# Audio.net
KiCad netlist of a schematic drawn in Altium Designer
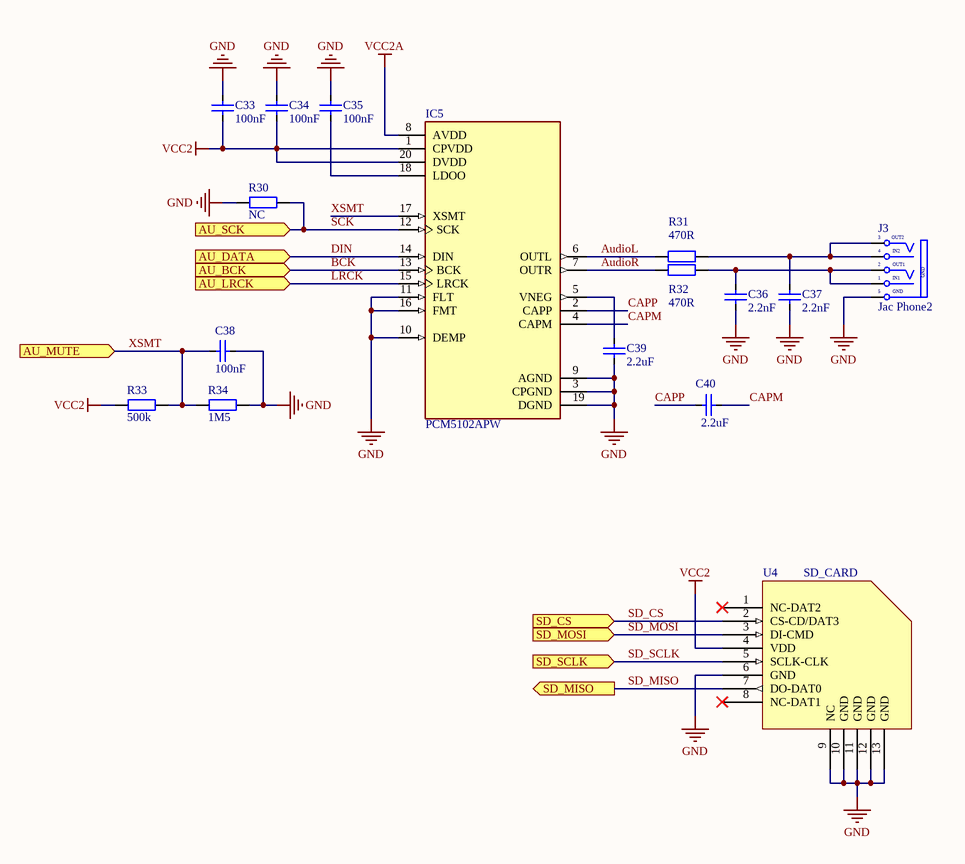
[diagram p0: Audio.SchDoc]

(export (version "E")
  (design (tool "Eeschema 10.0.6"))
  (components
    (comp (ref "C33")
      (value "100nF")
      (footprint "CAP_0603")
      (description "Capacitor")
      (fields (field (name "PUBLISHER") "Altium Limited"))
      (libsource (lib "My Library") (part "CapSMD"))
    )
    (comp (ref "C34")
      (value "100nF")
      (footprint "CAP_0603")
      (description "Capacitor")
      (fields (field (name "PUBLISHER") "Altium Limited"))
      (libsource (lib "My Library") (part "CapSMD"))
    )
    (comp (ref "C35")
      (value "100nF")
      (footprint "CAP_0603")
      (description "Capacitor")
      (fields (field (name "PUBLISHER") "Altium Limited"))
      (libsource (lib "My Library") (part "CapSMD"))
    )
    (comp (ref "C36")
      (value "2.2nF")
      (footprint "CAP_0603")
      (description "Capacitor")
      (fields (field (name "PUBLISHER") "Altium Limited"))
      (libsource (lib "My Library") (part "CapSMD"))
    )
    (comp (ref "C37")
      (value "2.2nF")
      (footprint "CAP_0603")
      (description "Capacitor")
      (fields (field (name "PUBLISHER") "Altium Limited"))
      (libsource (lib "My Library") (part "CapSMD"))
    )
    (comp (ref "C38")
      (value "100nF")
      (footprint "CAP_0603")
      (description "Capacitor")
      (fields (field (name "PUBLISHER") "Altium Limited"))
      (libsource (lib "My Library") (part "CapSMD"))
    )
    (comp (ref "C39")
      (value "2.2uF")
      (footprint "CAP_0603")
      (description "Capacitor")
      (fields (field (name "PUBLISHER") "Altium Limited"))
      (libsource (lib "My Library") (part "CapSMD"))
    )
    (comp (ref "C40")
      (value "2.2uF")
      (footprint "CAP_0603")
      (description "Capacitor")
      (fields (field (name "PUBLISHER") "Altium Limited"))
      (libsource (lib "My Library") (part "CapSMD"))
    )
    (comp (ref "IC5")
      (value "PCM5102APW")
      (footprint "TSSOP-20")
      (description "Audio decode")
      (libsource (lib "My Library") (part "PCM5102APW"))
    )
    (comp (ref "J3")
      (value "Jac Phone2")
      (footprint "JacPhone2")
      (description "Jac Phone Stereo")
      (fields (field (name "CREAT BY") "VanDungEvn@Gmail.com"))
      (libsource (lib "My Library") (part "Jac Phone2"))
    )
    (comp (ref "R30")
      (value "NC")
      (footprint "RES-SMD-0603")
      (description "Resistor SMD")
      (fields
        (field (name "MANUFACTURER") "Generic Components")
        (field (name "PUBLISHER") "Altium Hobart Technology Centre")
      )
      (libsource (lib "My Library") (part "Resistor - SMD"))
    )
    (comp (ref "R31")
      (value "470R")
      (footprint "RES-SMD-0603")
      (description "Resistor SMD")
      (fields
        (field (name "MANUFACTURER") "Generic Components")
        (field (name "PUBLISHER") "Altium Hobart Technology Centre")
      )
      (libsource (lib "My Library") (part "Resistor - SMD"))
    )
    (comp (ref "R32")
      (value "470R")
      (footprint "RES-SMD-0603")
      (description "Resistor SMD")
      (fields
        (field (name "MANUFACTURER") "Generic Components")
        (field (name "PUBLISHER") "Altium Hobart Technology Centre")
      )
      (libsource (lib "My Library") (part "Resistor - SMD"))
    )
    (comp (ref "R33")
      (value "500k")
      (footprint "RES-SMD-0603")
      (description "Resistor SMD")
      (fields
        (field (name "MANUFACTURER") "Generic Components")
        (field (name "PUBLISHER") "Altium Hobart Technology Centre")
      )
      (libsource (lib "My Library") (part "Resistor - SMD"))
    )
    (comp (ref "R34")
      (value "1M5")
      (footprint "RES-SMD-0603")
      (description "Resistor SMD")
      (fields
        (field (name "MANUFACTURER") "Generic Components")
        (field (name "PUBLISHER") "Altium Hobart Technology Centre")
      )
      (libsource (lib "My Library") (part "Resistor - SMD"))
    )
    (comp (ref "U4")
      (value "SD_CARD")
      (footprint "MICROSD2")
      (description "SD/MMC holder")
      (libsource (lib "My Library") (part "MicroSD"))
    )
  )
  (nets
    (net (code "1") (name "/AudioL") (class "Default")
      (node (ref "IC5") (pin "6") (pinfunction "OUTL_6") (pintype "output"))
      (node (ref "R31") (pin "2") (pinfunction "2_2") (pintype "passive"))
    )
    (net (code "2") (name "/AudioR") (class "Default")
      (node (ref "IC5") (pin "7") (pinfunction "OUTR_7") (pintype "output"))
      (node (ref "R32") (pin "2") (pinfunction "2_2") (pintype "passive"))
    )
    (net (code "3") (name "/BCK") (class "Default")
      (node (ref "IC5") (pin "13") (pinfunction "BCK_13") (pintype "input"))
    )
    (net (code "4") (name "/CAPM") (class "Default")
      (node (ref "C40") (pin "2") (pinfunction "2_2") (pintype "passive"))
      (node (ref "IC5") (pin "4") (pinfunction "CAPM_4") (pintype "passive"))
    )
    (net (code "5") (name "/CAPP") (class "Default")
      (node (ref "C40") (pin "1") (pinfunction "1_1") (pintype "passive"))
      (node (ref "IC5") (pin "2") (pinfunction "CAPP_2") (pintype "passive"))
    )
    (net (code "6") (name "/DIN") (class "Default")
      (node (ref "IC5") (pin "14") (pinfunction "DIN_14") (pintype "input"))
    )
    (net (code "7") (name "/LRCK") (class "Default")
      (node (ref "IC5") (pin "15") (pinfunction "LRCK_15") (pintype "input"))
    )
    (net (code "8") (name "/SCK") (class "Default")
      (node (ref "IC5") (pin "12") (pinfunction "SCK_12") (pintype "input"))
      (node (ref "R30") (pin "2") (pinfunction "2_2") (pintype "passive"))
    )
    (net (code "9") (name "/SD_CS") (class "Default")
      (node (ref "U4") (pin "2") (pinfunction "CS-CD/DAT3_2") (pintype "input"))
    )
    (net (code "10") (name "/SD_MISO") (class "Default")
      (node (ref "U4") (pin "7") (pinfunction "DO-DAT0_7") (pintype "output"))
    )
    (net (code "11") (name "/SD_MOSI") (class "Default")
      (node (ref "U4") (pin "3") (pinfunction "DI-CMD_3") (pintype "input"))
    )
    (net (code "12") (name "/SD_SCLK") (class "Default")
      (node (ref "U4") (pin "5") (pinfunction "SCLK-CLK_5") (pintype "input"))
    )
    (net (code "13") (name "/XSMT") (class "Default")
      (node (ref "C38") (pin "1") (pinfunction "1_1") (pintype "passive"))
      (node (ref "IC5") (pin "17") (pinfunction "XSMT_17") (pintype "input"))
      (node (ref "R33") (pin "2") (pinfunction "2_2") (pintype "passive"))
      (node (ref "R34") (pin "1") (pinfunction "1_1") (pintype "passive"))
    )
    (net (code "14") (name "GND") (class "Default")
      (node (ref "C33") (pin "1") (pinfunction "1_1") (pintype "passive"))
      (node (ref "C34") (pin "1") (pinfunction "1_1") (pintype "passive"))
      (node (ref "C35") (pin "1") (pinfunction "1_1") (pintype "passive"))
      (node (ref "C36") (pin "1") (pinfunction "1_1") (pintype "passive"))
      (node (ref "C37") (pin "1") (pinfunction "1_1") (pintype "passive"))
      (node (ref "C38") (pin "2") (pinfunction "2_2") (pintype "passive"))
      (node (ref "C39") (pin "1") (pinfunction "1_1") (pintype "passive"))
      (node (ref "IC5") (pin "10") (pinfunction "DEMP_10") (pintype "input"))
      (node (ref "IC5") (pin "11") (pinfunction "FLT_11") (pintype "input"))
      (node (ref "IC5") (pin "16") (pinfunction "FMT_16") (pintype "input"))
      (node (ref "IC5") (pin "19") (pinfunction "DGND_19") (pintype "power_in"))
      (node (ref "IC5") (pin "3") (pinfunction "CPGND_3") (pintype "power_in"))
      (node (ref "IC5") (pin "9") (pinfunction "AGND_9") (pintype "power_in"))
      (node (ref "J3") (pin "5") (pinfunction "GND_5") (pintype "passive"))
      (node (ref "R30") (pin "1") (pinfunction "1_1") (pintype "passive"))
      (node (ref "R34") (pin "2") (pinfunction "2_2") (pintype "passive"))
      (node (ref "U4") (pin "10") (pinfunction "GND_10") (pintype "passive"))
      (node (ref "U4") (pin "11") (pinfunction "GND_11") (pintype "passive"))
      (node (ref "U4") (pin "12") (pinfunction "GND_12") (pintype "passive"))
      (node (ref "U4") (pin "13") (pinfunction "GND_13") (pintype "passive"))
      (node (ref "U4") (pin "6") (pinfunction "GND_6") (pintype "passive"))
      (node (ref "U4") (pin "9") (pinfunction "NC_9") (pintype "passive"))
    )
    (net (code "15") (name "Net-(C36-Pad2)") (class "Default")
      (node (ref "C36") (pin "2") (pinfunction "2_2") (pintype "passive"))
      (node (ref "J3") (pin "1") (pinfunction "S1_1") (pintype "power_in"))
      (node (ref "J3") (pin "2") (pinfunction "S1_2") (pintype "passive"))
      (node (ref "R32") (pin "1") (pinfunction "1_1") (pintype "passive"))
    )
    (net (code "16") (name "Net-(IC5-LDOO)") (class "Default")
      (node (ref "C35") (pin "2") (pinfunction "2_2") (pintype "passive"))
      (node (ref "IC5") (pin "18") (pinfunction "LDOO_18") (pintype "power_in"))
    )
    (net (code "17") (name "Net-(IC5-VNEG)") (class "Default")
      (node (ref "C39") (pin "2") (pinfunction "2_2") (pintype "passive"))
      (node (ref "IC5") (pin "5") (pinfunction "VNEG_5") (pintype "output"))
    )
    (net (code "18") (name "Net-(J3-S)") (class "Default")
      (node (ref "C37") (pin "2") (pinfunction "2_2") (pintype "passive"))
      (node (ref "J3") (pin "3") (pinfunction "TN_3") (pintype "passive"))
      (node (ref "J3") (pin "4") (pinfunction "S_4") (pintype "power_in"))
      (node (ref "R31") (pin "1") (pinfunction "1_1") (pintype "passive"))
    )
    (net (code "19") (name "VCC2") (class "Default")
      (node (ref "C33") (pin "2") (pinfunction "2_2") (pintype "passive"))
      (node (ref "C34") (pin "2") (pinfunction "2_2") (pintype "passive"))
      (node (ref "IC5") (pin "1") (pinfunction "CPVDD_1") (pintype "power_in"))
      (node (ref "IC5") (pin "20") (pinfunction "DVDD_20") (pintype "power_in"))
      (node (ref "R33") (pin "1") (pinfunction "1_1") (pintype "passive"))
      (node (ref "U4") (pin "4") (pinfunction "VDD_4") (pintype "passive"))
    )
    (net (code "20") (name "VCC2A") (class "Default")
      (node (ref "IC5") (pin "8") (pinfunction "AVDD_8") (pintype "power_in"))
    )
    (net (code "21") (name "unconnected-(U4-NC-DAT1-Pad8)") (class "Default")
      (node (ref "U4") (pin "8") (pinfunction "NC-DAT1_8") (pintype "passive+no_connect"))
    )
    (net (code "22") (name "unconnected-(U4-NC-DAT2-Pad1)") (class "Default")
      (node (ref "U4") (pin "1") (pinfunction "NC-DAT2_1") (pintype "passive+no_connect"))
    )
  )
)
